# Freqy_Lights_1v1.net
KiCad netlist of a schematic drawn in EAGLE
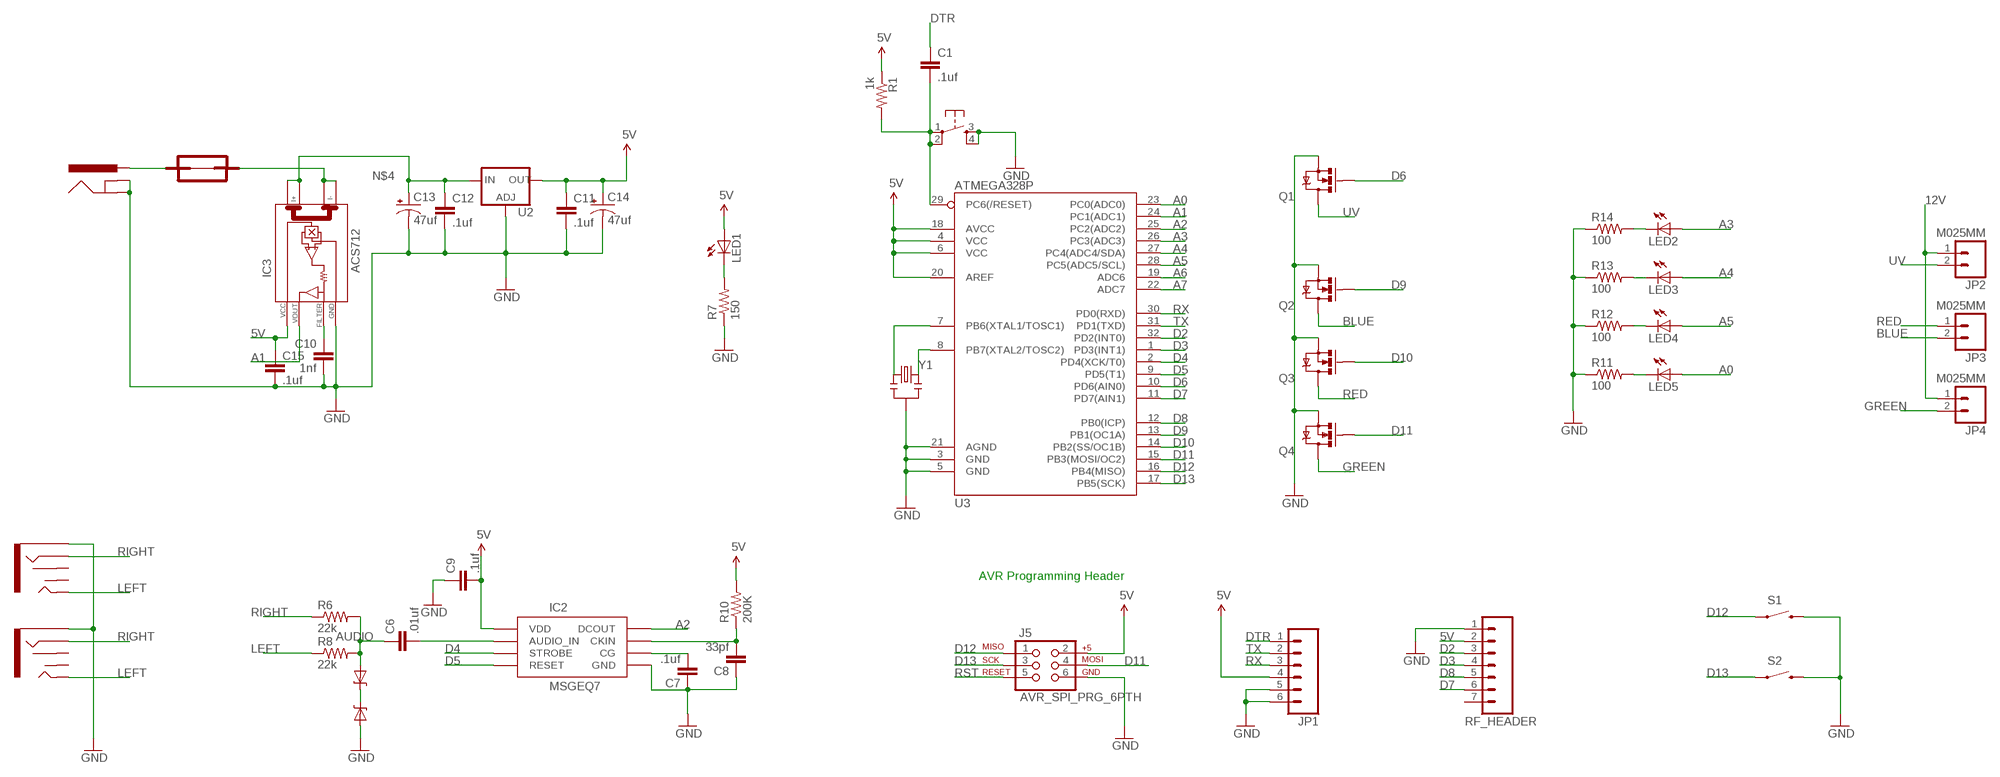
[diagram p0: schematic, sheet 1]

(export (version "E")
  (design (tool "Eeschema 10.0.6"))
  (components
    (comp (ref "AJ1")
      (value "SC1488-1-ND_SMD_AUDIO_3.5")
      (footprint "eagle-import:3.5MM_SMD_AUDIO_SC1488-1-ND")
      (libsource (lib "eagle-import") (part "SC1488-1-ND_SMD_AUDIO_3.5"))
    )
    (comp (ref "AJ2")
      (value "SC1488-1-ND_SMD_AUDIO_3.5")
      (footprint "eagle-import:3.5MM_SMD_AUDIO_SC1488-1-ND")
      (libsource (lib "eagle-import") (part "SC1488-1-ND_SMD_AUDIO_3.5"))
    )
    (comp (ref "BJ1")
      (value "CP-202BH-ND_POWERJACK")
      (footprint "eagle-import:POWER_JACK_CP-202BH-ND")
      (libsource (lib "eagle-import") (part "CP-202BH-ND_POWERJACK"))
    )
    (comp (ref "C1")
      (value ".1uf")
      (footprint "eagle-import:1206")
      (libsource (lib "eagle-import") (part "CAP1206"))
    )
    (comp (ref "C6")
      (value ".01uf")
      (footprint "eagle-import:1206")
      (libsource (lib "eagle-import") (part "CAP1206"))
    )
    (comp (ref "C7")
      (value ".1uf")
      (footprint "eagle-import:1206")
      (libsource (lib "eagle-import") (part "CAP1206"))
    )
    (comp (ref "C8")
      (value "33pf")
      (footprint "eagle-import:1206")
      (libsource (lib "eagle-import") (part "CAP1206"))
    )
    (comp (ref "C9")
      (value ".1uf")
      (footprint "eagle-import:1206")
      (libsource (lib "eagle-import") (part "CAP1206"))
    )
    (comp (ref "C10")
      (value "1nf")
      (footprint "eagle-import:1206")
      (libsource (lib "eagle-import") (part "CAP1206"))
    )
    (comp (ref "C11")
      (value ".1uf")
      (footprint "eagle-import:1206")
      (libsource (lib "eagle-import") (part "CAP1206"))
    )
    (comp (ref "C12")
      (value ".1uf")
      (footprint "eagle-import:1206")
      (libsource (lib "eagle-import") (part "CAP1206"))
    )
    (comp (ref "C13")
      (value "47uf")
      (footprint "eagle-import:SMD_47UF_CAP_493-2202-1-ND")
      (libsource (lib "eagle-import") (part "493-2202-1-ND_SMD_CAP"))
    )
    (comp (ref "C14")
      (value "47uf")
      (footprint "eagle-import:SMD_47UF_CAP_493-2202-1-ND")
      (libsource (lib "eagle-import") (part "493-2202-1-ND_SMD_CAP"))
    )
    (comp (ref "C15")
      (value ".1uf")
      (footprint "eagle-import:1206")
      (libsource (lib "eagle-import") (part "CAP1206"))
    )
    (comp (ref "F1")
      (value "SSQ12")
      (footprint "eagle-import:SSQ12")
      (libsource (lib "eagle-import") (part "SSQ12"))
    )
    (comp (ref "IC2")
      (value "MSGEQ7SOIC")
      (footprint "eagle-import:SOIC8")
      (libsource (lib "eagle-import") (part "MSGEQ7SOIC"))
    )
    (comp (ref "IC3")
      (value "ACS712")
      (footprint "eagle-import:SO08")
      (libsource (lib "eagle-import") (part "ACS712"))
    )
    (comp (ref "J5")
      (value "AVR_SPI_PRG_6PTH")
      (footprint "eagle-import:2X3")
      (libsource (lib "eagle-import") (part "AVR_SPI_PRG_6PTH"))
    )
    (comp (ref "JP1")
      (value "M06SIP")
      (footprint "eagle-import:1X06")
      (libsource (lib "eagle-import") (part "M06SIP"))
    )
    (comp (ref "JP2")
      (value "M025MM")
      (footprint "eagle-import:SCREWTERMINAL-5MM-2")
      (libsource (lib "eagle-import") (part "M025MM"))
    )
    (comp (ref "JP3")
      (value "M025MM")
      (footprint "eagle-import:SCREWTERMINAL-5MM-2")
      (libsource (lib "eagle-import") (part "M025MM"))
    )
    (comp (ref "JP4")
      (value "M025MM")
      (footprint "eagle-import:SCREWTERMINAL-5MM-2")
      (libsource (lib "eagle-import") (part "M025MM"))
    )
    (comp (ref "LED1")
      (value "LED1206")
      (footprint "eagle-import:LED-1206")
      (libsource (lib "eagle-import") (part "LED1206"))
    )
    (comp (ref "LED2")
      (value "LED1206")
      (footprint "eagle-import:LED-1206")
      (libsource (lib "eagle-import") (part "LED1206"))
    )
    (comp (ref "LED3")
      (value "LED1206")
      (footprint "eagle-import:LED-1206")
      (libsource (lib "eagle-import") (part "LED1206"))
    )
    (comp (ref "LED4")
      (value "LED1206")
      (footprint "eagle-import:LED-1206")
      (libsource (lib "eagle-import") (part "LED1206"))
    )
    (comp (ref "LED5")
      (value "LED1206")
      (footprint "eagle-import:LED-1206")
      (libsource (lib "eagle-import") (part "LED1206"))
    )
    (comp (ref "P1")
      (value "CKN9085CT-ND_SMT_PUSHBUTTON")
      (footprint "eagle-import:SMT_PUSHBUTTON_CKN9085CT-ND")
      (libsource (lib "eagle-import") (part "CKN9085CT-ND_SMT_PUSHBUTTON"))
    )
    (comp (ref "Q1")
      (value "MOSFET-NCHANNELBSS138")
      (footprint "eagle-import:SOT23")
      (libsource (lib "eagle-import") (part "MOSFET-NCHANNELBSS138"))
    )
    (comp (ref "Q2")
      (value "MOSFET-NCHANNELBSS138")
      (footprint "eagle-import:SOT23")
      (libsource (lib "eagle-import") (part "MOSFET-NCHANNELBSS138"))
    )
    (comp (ref "Q3")
      (value "MOSFET-NCHANNELBSS138")
      (footprint "eagle-import:SOT23")
      (libsource (lib "eagle-import") (part "MOSFET-NCHANNELBSS138"))
    )
    (comp (ref "Q4")
      (value "MOSFET-NCHANNELBSS138")
      (footprint "eagle-import:SOT23")
      (libsource (lib "eagle-import") (part "MOSFET-NCHANNELBSS138"))
    )
    (comp (ref "R1")
      (value "1k")
      (footprint "eagle-import:1206")
      (libsource (lib "eagle-import") (part "RESISTOR1206"))
    )
    (comp (ref "R6")
      (value "22k")
      (footprint "eagle-import:1206")
      (libsource (lib "eagle-import") (part "RESISTOR1206"))
    )
    (comp (ref "R7")
      (value "150")
      (footprint "eagle-import:1206")
      (libsource (lib "eagle-import") (part "RESISTOR1206"))
    )
    (comp (ref "R8")
      (value "22k")
      (footprint "eagle-import:1206")
      (libsource (lib "eagle-import") (part "RESISTOR1206"))
    )
    (comp (ref "R10")
      (value "200K")
      (footprint "eagle-import:1206")
      (libsource (lib "eagle-import") (part "RESISTOR1206"))
    )
    (comp (ref "R11")
      (value "100")
      (footprint "eagle-import:1206")
      (libsource (lib "eagle-import") (part "RESISTOR1206"))
    )
    (comp (ref "R12")
      (value "100")
      (footprint "eagle-import:1206")
      (libsource (lib "eagle-import") (part "RESISTOR1206"))
    )
    (comp (ref "R13")
      (value "100")
      (footprint "eagle-import:1206")
      (libsource (lib "eagle-import") (part "RESISTOR1206"))
    )
    (comp (ref "R14")
      (value "100")
      (footprint "eagle-import:1206")
      (libsource (lib "eagle-import") (part "RESISTOR1206"))
    )
    (comp (ref "RF_HEADER")
      (value "M07")
      (footprint "eagle-import:1X07")
      (libsource (lib "eagle-import") (part "M07"))
    )
    (comp (ref "S1")
      (value "SWITCH-MOMENTARY-2PTH")
      (footprint "eagle-import:TACTILE-PTH")
      (libsource (lib "eagle-import") (part "SWITCH-MOMENTARY-2PTH"))
    )
    (comp (ref "S2")
      (value "SWITCH-MOMENTARY-2PTH")
      (footprint "eagle-import:TACTILE-PTH")
      (libsource (lib "eagle-import") (part "SWITCH-MOMENTARY-2PTH"))
    )
    (comp (ref "U$10")
      (value "MM3Z3V3ST1GOSCT-ND_3V_DIODE")
      (footprint "eagle-import:3V_DIODE_MM3Z3V3ST1GOSCT-ND")
      (libsource (lib "eagle-import") (part "MM3Z3V3ST1GOSCT-ND_3V_DIODE"))
    )
    (comp (ref "U$11")
      (value "MM3Z3V3ST1GOSCT-ND_3V_DIODE")
      (footprint "eagle-import:3V_DIODE_MM3Z3V3ST1GOSCT-ND")
      (libsource (lib "eagle-import") (part "MM3Z3V3ST1GOSCT-ND_3V_DIODE"))
    )
    (comp (ref "U2")
      (value "V_REG_317SMD")
      (footprint "eagle-import:SOT223")
      (libsource (lib "eagle-import") (part "V_REG_317SMD"))
    )
    (comp (ref "U3")
      (value "ATMEGA328P")
      (footprint "eagle-import:TQFP32-08")
      (libsource (lib "eagle-import") (part "ATMEGA328_SMT"))
    )
    (comp (ref "Y1")
      (value "RESONATORPTH")
      (footprint "eagle-import:RESONATOR-PTH")
      (libsource (lib "eagle-import") (part "RESONATORPTH"))
    )
  )
  (nets
    (net (code "1") (name "/12V") (class "Default")
      (node (ref "C12") (pin "1") (pinfunction "1_1") (pintype "passive"))
      (node (ref "C13") (pin "P$2") (pinfunction "+_P$2") (pintype "passive"))
      (node (ref "IC3") (pin "1") (pinfunction "I+_0_1") (pintype "bidirectional"))
      (node (ref "IC3") (pin "2") (pinfunction "I+_1_2") (pintype "bidirectional"))
      (node (ref "JP2") (pin "1") (pinfunction "1_1") (pintype "passive"))
      (node (ref "JP4") (pin "1") (pinfunction "1_1") (pintype "passive"))
      (node (ref "U2") (pin "3") (pinfunction "IN_3") (pintype "input"))
    )
    (net (code "2") (name "/A0") (class "Default")
      (node (ref "LED5") (pin "A") (pinfunction "A_A") (pintype "passive"))
      (node (ref "U3") (pin "23") (pinfunction "PC0(ADC0)_23") (pintype "bidirectional"))
    )
    (net (code "3") (name "/A1") (class "Default")
      (node (ref "IC3") (pin "7") (pinfunction "VOUT_7") (pintype "output"))
      (node (ref "U3") (pin "24") (pinfunction "PC1(ADC1)_24") (pintype "bidirectional"))
    )
    (net (code "4") (name "/A2") (class "Default")
      (node (ref "IC2") (pin "3") (pinfunction "DCOUT_3") (pintype "bidirectional"))
      (node (ref "U3") (pin "25") (pinfunction "PC2(ADC2)_25") (pintype "bidirectional"))
    )
    (net (code "5") (name "/A3") (class "Default")
      (node (ref "LED2") (pin "A") (pinfunction "A_A") (pintype "passive"))
      (node (ref "U3") (pin "26") (pinfunction "PC3(ADC3)_26") (pintype "bidirectional"))
    )
    (net (code "6") (name "/A4") (class "Default")
      (node (ref "LED3") (pin "A") (pinfunction "A_A") (pintype "passive"))
      (node (ref "U3") (pin "27") (pinfunction "PC4(ADC4/SDA)_27") (pintype "bidirectional"))
    )
    (net (code "7") (name "/A5") (class "Default")
      (node (ref "LED4") (pin "A") (pinfunction "A_A") (pintype "passive"))
      (node (ref "U3") (pin "28") (pinfunction "PC5(ADC5/SCL)_28") (pintype "bidirectional"))
    )
    (net (code "8") (name "/A6") (class "Default")
      (node (ref "U3") (pin "19") (pinfunction "ADC6_19") (pintype "bidirectional"))
    )
    (net (code "9") (name "/A7") (class "Default")
      (node (ref "U3") (pin "22") (pinfunction "ADC7_22") (pintype "bidirectional"))
    )
    (net (code "10") (name "/AUDIO") (class "Default")
      (node (ref "C6") (pin "1") (pinfunction "1_1") (pintype "passive"))
      (node (ref "R6") (pin "2") (pinfunction "2_2") (pintype "passive"))
      (node (ref "R8") (pin "2") (pinfunction "2_2") (pintype "passive"))
      (node (ref "U$11") (pin "P$2") (pinfunction "A_P$2") (pintype "passive"))
    )
    (net (code "11") (name "/BLUE") (class "Default")
      (node (ref "JP3") (pin "2") (pinfunction "2_2") (pintype "passive"))
      (node (ref "Q2") (pin "3") (pinfunction "D_3") (pintype "passive"))
    )
    (net (code "12") (name "/D2") (class "Default")
      (node (ref "RF_HEADER") (pin "3") (pinfunction "3_3") (pintype "passive"))
      (node (ref "U3") (pin "32") (pinfunction "PD2(INT0)_32") (pintype "bidirectional"))
    )
    (net (code "13") (name "/D3") (class "Default")
      (node (ref "RF_HEADER") (pin "4") (pinfunction "4_4") (pintype "passive"))
      (node (ref "U3") (pin "1") (pinfunction "PD3(INT1)_1") (pintype "bidirectional"))
    )
    (net (code "14") (name "/D4") (class "Default")
      (node (ref "IC2") (pin "4") (pinfunction "STROBE_4") (pintype "input"))
      (node (ref "U3") (pin "2") (pinfunction "PD4(XCK/T0)_2") (pintype "bidirectional"))
    )
    (net (code "15") (name "/D5") (class "Default")
      (node (ref "IC2") (pin "7") (pinfunction "RESET_7") (pintype "input"))
      (node (ref "U3") (pin "9") (pinfunction "PD5(T1)_9") (pintype "bidirectional"))
    )
    (net (code "16") (name "/D6") (class "Default")
      (node (ref "Q1") (pin "1") (pinfunction "G_1") (pintype "passive"))
      (node (ref "U3") (pin "10") (pinfunction "PD6(AIN0)_10") (pintype "bidirectional"))
    )
    (net (code "17") (name "/D7") (class "Default")
      (node (ref "RF_HEADER") (pin "6") (pinfunction "6_6") (pintype "passive"))
      (node (ref "U3") (pin "11") (pinfunction "PD7(AIN1)_11") (pintype "bidirectional"))
    )
    (net (code "18") (name "/D8") (class "Default")
      (node (ref "RF_HEADER") (pin "5") (pinfunction "5_5") (pintype "passive"))
      (node (ref "U3") (pin "12") (pinfunction "PB0(ICP)_12") (pintype "bidirectional"))
    )
    (net (code "19") (name "/D9") (class "Default")
      (node (ref "Q2") (pin "1") (pinfunction "G_1") (pintype "passive"))
      (node (ref "U3") (pin "13") (pinfunction "PB1(OC1A)_13") (pintype "bidirectional"))
    )
    (net (code "20") (name "/D10") (class "Default")
      (node (ref "Q3") (pin "1") (pinfunction "G_1") (pintype "passive"))
      (node (ref "U3") (pin "14") (pinfunction "PB2(SS/OC1B)_14") (pintype "bidirectional"))
    )
    (net (code "21") (name "/D11") (class "Default")
      (node (ref "J5") (pin "4") (pinfunction "4_4") (pintype "passive"))
      (node (ref "Q4") (pin "1") (pinfunction "G_1") (pintype "passive"))
      (node (ref "U3") (pin "15") (pinfunction "PB3(MOSI/OC2)_15") (pintype "bidirectional"))
    )
    (net (code "22") (name "/D12") (class "Default")
      (node (ref "J5") (pin "1") (pinfunction "1_1") (pintype "passive"))
      (node (ref "S1") (pin "1") (pinfunction "1_1") (pintype "passive"))
      (node (ref "U3") (pin "16") (pinfunction "PB4(MISO)_16") (pintype "bidirectional"))
    )
    (net (code "23") (name "/D13") (class "Default")
      (node (ref "J5") (pin "3") (pinfunction "3_3") (pintype "passive"))
      (node (ref "S2") (pin "1") (pinfunction "1_1") (pintype "passive"))
      (node (ref "U3") (pin "17") (pinfunction "PB5(SCK)_17") (pintype "bidirectional"))
    )
    (net (code "24") (name "/DTR") (class "Default")
      (node (ref "C1") (pin "1") (pinfunction "1_1") (pintype "passive"))
      (node (ref "JP1") (pin "1") (pinfunction "1_1") (pintype "passive"))
    )
    (net (code "25") (name "/GREEN") (class "Default")
      (node (ref "JP4") (pin "2") (pinfunction "2_2") (pintype "passive"))
      (node (ref "Q4") (pin "3") (pinfunction "D_3") (pintype "passive"))
    )
    (net (code "26") (name "/LEFT") (class "Default")
      (node (ref "AJ1") (pin "TIP") (pinfunction "TIP_TIP") (pintype "bidirectional"))
      (node (ref "AJ2") (pin "TIP") (pinfunction "TIP_TIP") (pintype "bidirectional"))
      (node (ref "R8") (pin "1") (pinfunction "1_1") (pintype "passive"))
    )
    (net (code "27") (name "/N$4") (class "Default")
      (node (ref "F1") (pin "P$2") (pinfunction "P$2_P$2") (pintype "bidirectional"))
      (node (ref "IC3") (pin "3") (pinfunction "I-_0_3") (pintype "bidirectional"))
      (node (ref "IC3") (pin "4") (pinfunction "I-_1_4") (pintype "bidirectional"))
    )
    (net (code "28") (name "/RED") (class "Default")
      (node (ref "JP3") (pin "1") (pinfunction "1_1") (pintype "passive"))
      (node (ref "Q3") (pin "3") (pinfunction "D_3") (pintype "passive"))
    )
    (net (code "29") (name "/RIGHT") (class "Default")
      (node (ref "AJ1") (pin "SLEEVE") (pinfunction "SLEEVE_SLEEVE") (pintype "bidirectional"))
      (node (ref "AJ2") (pin "SLEEVE") (pinfunction "SLEEVE_SLEEVE") (pintype "bidirectional"))
      (node (ref "R6") (pin "1") (pinfunction "1_1") (pintype "passive"))
    )
    (net (code "30") (name "/RST") (class "Default")
      (node (ref "C1") (pin "2") (pinfunction "2_2") (pintype "passive"))
      (node (ref "J5") (pin "5") (pinfunction "5_5") (pintype "passive"))
      (node (ref "P1") (pin "1") (pinfunction "1_1") (pintype "passive"))
      (node (ref "P1") (pin "2") (pinfunction "2_2") (pintype "passive"))
      (node (ref "R1") (pin "2") (pinfunction "2_2") (pintype "passive"))
      (node (ref "U3") (pin "29") (pinfunction "PC6(/RESET)_29") (pintype "bidirectional"))
    )
    (net (code "31") (name "/RX") (class "Default")
      (node (ref "JP1") (pin "3") (pinfunction "3_3") (pintype "passive"))
      (node (ref "U3") (pin "30") (pinfunction "PD0(RXD)_30") (pintype "bidirectional"))
    )
    (net (code "32") (name "/TX") (class "Default")
      (node (ref "JP1") (pin "2") (pinfunction "2_2") (pintype "passive"))
      (node (ref "U3") (pin "31") (pinfunction "PD1(TXD)_31") (pintype "bidirectional"))
    )
    (net (code "33") (name "/UV") (class "Default")
      (node (ref "JP2") (pin "2") (pinfunction "2_2") (pintype "passive"))
      (node (ref "Q1") (pin "3") (pinfunction "D_3") (pintype "passive"))
    )
    (net (code "34") (name "5V") (class "Default")
      (node (ref "C11") (pin "1") (pinfunction "1_1") (pintype "passive"))
      (node (ref "C14") (pin "P$2") (pinfunction "+_P$2") (pintype "passive"))
      (node (ref "C15") (pin "1") (pinfunction "1_1") (pintype "passive"))
      (node (ref "C9") (pin "2") (pinfunction "2_2") (pintype "passive"))
      (node (ref "IC2") (pin "1") (pinfunction "VDD_1") (pintype "input"))
      (node (ref "IC3") (pin "8") (pinfunction "VCC_8") (pintype "power_in"))
      (node (ref "J5") (pin "2") (pinfunction "2_2") (pintype "passive"))
      (node (ref "JP1") (pin "4") (pinfunction "4_4") (pintype "passive"))
      (node (ref "LED1") (pin "A") (pinfunction "A_A") (pintype "passive"))
      (node (ref "R1") (pin "1") (pinfunction "1_1") (pintype "passive"))
      (node (ref "R10") (pin "2") (pinfunction "2_2") (pintype "passive"))
      (node (ref "RF_HEADER") (pin "2") (pinfunction "2_2") (pintype "passive"))
      (node (ref "U2") (pin "2") (pinfunction "OUT_2") (pintype "output"))
      (node (ref "U3") (pin "18") (pinfunction "AVCC_18") (pintype "bidirectional"))
      (node (ref "U3") (pin "20") (pinfunction "AREF_20") (pintype "bidirectional"))
      (node (ref "U3") (pin "4") (pinfunction "VCC_4") (pintype "bidirectional"))
      (node (ref "U3") (pin "6") (pinfunction "VCC_6") (pintype "bidirectional"))
    )
    (net (code "35") (name "GND") (class "Default")
      (node (ref "AJ1") (pin "RING") (pinfunction "RING_RING") (pintype "bidirectional"))
      (node (ref "AJ2") (pin "RING") (pinfunction "RING_RING") (pintype "bidirectional"))
      (node (ref "BJ1") (pin "GND") (pinfunction "GND_GND") (pintype "bidirectional"))
      (node (ref "BJ1") (pin "GNDBRK") (pinfunction "GNDBREAK_GNDBRK") (pintype "bidirectional"))
      (node (ref "C10") (pin "2") (pinfunction "2_2") (pintype "passive"))
      (node (ref "C11") (pin "2") (pinfunction "2_2") (pintype "passive"))
      (node (ref "C12") (pin "2") (pinfunction "2_2") (pintype "passive"))
      (node (ref "C13") (pin "P$1") (pinfunction "-_P$1") (pintype "passive"))
      (node (ref "C14") (pin "P$1") (pinfunction "-_P$1") (pintype "passive"))
      (node (ref "C15") (pin "2") (pinfunction "2_2") (pintype "passive"))
      (node (ref "C7") (pin "1") (pinfunction "1_1") (pintype "passive"))
      (node (ref "C8") (pin "1") (pinfunction "1_1") (pintype "passive"))
      (node (ref "C9") (pin "1") (pinfunction "1_1") (pintype "passive"))
      (node (ref "IC2") (pin "2") (pinfunction "GND_2") (pintype "bidirectional"))
      (node (ref "IC3") (pin "5") (pinfunction "GND_5") (pintype "power_in"))
      (node (ref "J5") (pin "6") (pinfunction "6_6") (pintype "passive"))
      (node (ref "JP1") (pin "5") (pinfunction "5_5") (pintype "passive"))
      (node (ref "JP1") (pin "6") (pinfunction "6_6") (pintype "passive"))
      (node (ref "P1") (pin "3") (pinfunction "3_3") (pintype "passive"))
      (node (ref "P1") (pin "4") (pinfunction "4_4") (pintype "passive"))
      (node (ref "Q1") (pin "2") (pinfunction "S_2") (pintype "passive"))
      (node (ref "Q2") (pin "2") (pinfunction "S_2") (pintype "passive"))
      (node (ref "Q3") (pin "2") (pinfunction "S_2") (pintype "passive"))
      (node (ref "Q4") (pin "2") (pinfunction "S_2") (pintype "passive"))
      (node (ref "R11") (pin "1") (pinfunction "1_1") (pintype "passive"))
      (node (ref "R12") (pin "1") (pinfunction "1_1") (pintype "passive"))
      (node (ref "R13") (pin "1") (pinfunction "1_1") (pintype "passive"))
      (node (ref "R14") (pin "1") (pinfunction "1_1") (pintype "passive"))
      (node (ref "R7") (pin "1") (pinfunction "1_1") (pintype "passive"))
      (node (ref "RF_HEADER") (pin "1") (pinfunction "1_1") (pintype "passive"))
      (node (ref "S1") (pin "3") (pinfunction "2_3") (pintype "passive"))
      (node (ref "S2") (pin "3") (pinfunction "2_3") (pintype "passive"))
      (node (ref "U$10") (pin "P$2") (pinfunction "A_P$2") (pintype "passive"))
      (node (ref "U2") (pin "1") (pinfunction "ADJ_1") (pintype "input"))
      (node (ref "U3") (pin "21") (pinfunction "AGND_21") (pintype "bidirectional"))
      (node (ref "U3") (pin "3") (pinfunction "GND_3") (pintype "bidirectional"))
      (node (ref "U3") (pin "5") (pinfunction "GND_5") (pintype "bidirectional"))
      (node (ref "Y1") (pin "2") (pinfunction "2_2") (pintype "passive"))
    )
    (net (code "36") (name "Net-(BJ1-PadPWR)") (class "Default")
      (node (ref "BJ1") (pin "PWR") (pinfunction "PWR_PWR") (pintype "bidirectional"))
      (node (ref "F1") (pin "P$1") (pinfunction "P$1_P$1") (pintype "bidirectional"))
    )
    (net (code "37") (name "Net-(IC2-AUDIO_IN)") (class "Default")
      (node (ref "C6") (pin "2") (pinfunction "2_2") (pintype "passive"))
      (node (ref "IC2") (pin "5") (pinfunction "AUDIO_IN_5") (pintype "input"))
    )
    (net (code "38") (name "Net-(IC2-CG)") (class "Default")
      (node (ref "C7") (pin "2") (pinfunction "2_2") (pintype "passive"))
      (node (ref "IC2") (pin "6") (pinfunction "CG_6") (pintype "bidirectional"))
    )
    (net (code "39") (name "Net-(IC2-CKIN)") (class "Default")
      (node (ref "C8") (pin "2") (pinfunction "2_2") (pintype "passive"))
      (node (ref "IC2") (pin "8") (pinfunction "CKIN_8") (pintype "bidirectional"))
      (node (ref "R10") (pin "1") (pinfunction "1_1") (pintype "passive"))
    )
    (net (code "40") (name "Net-(IC3-FILTER)") (class "Default")
      (node (ref "C10") (pin "1") (pinfunction "1_1") (pintype "passive"))
      (node (ref "IC3") (pin "6") (pinfunction "FILTER_6") (pintype "bidirectional"))
    )
    (net (code "41") (name "Net-(LED1-PadC)") (class "Default")
      (node (ref "LED1") (pin "C") (pinfunction "C_C") (pintype "passive"))
      (node (ref "R7") (pin "2") (pinfunction "2_2") (pintype "passive"))
    )
    (net (code "42") (name "Net-(LED2-PadC)") (class "Default")
      (node (ref "LED2") (pin "C") (pinfunction "C_C") (pintype "passive"))
      (node (ref "R14") (pin "2") (pinfunction "2_2") (pintype "passive"))
    )
    (net (code "43") (name "Net-(LED3-PadC)") (class "Default")
      (node (ref "LED3") (pin "C") (pinfunction "C_C") (pintype "passive"))
      (node (ref "R13") (pin "2") (pinfunction "2_2") (pintype "passive"))
    )
    (net (code "44") (name "Net-(LED4-PadC)") (class "Default")
      (node (ref "LED4") (pin "C") (pinfunction "C_C") (pintype "passive"))
      (node (ref "R12") (pin "2") (pinfunction "2_2") (pintype "passive"))
    )
    (net (code "45") (name "Net-(LED5-PadC)") (class "Default")
      (node (ref "LED5") (pin "C") (pinfunction "C_C") (pintype "passive"))
      (node (ref "R11") (pin "2") (pinfunction "2_2") (pintype "passive"))
    )
    (net (code "46") (name "Net-(U$10-C)") (class "Default")
      (node (ref "U$10") (pin "P$1") (pinfunction "C_P$1") (pintype "passive"))
      (node (ref "U$11") (pin "P$1") (pinfunction "C_P$1") (pintype "passive"))
    )
    (net (code "47") (name "Net-(U3-PB6(XTAL1{slash}TOSC1))") (class "Default")
      (node (ref "U3") (pin "7") (pinfunction "PB6(XTAL1/TOSC1)_7") (pintype "bidirectional"))
      (node (ref "Y1") (pin "1") (pinfunction "1_1") (pintype "passive"))
    )
    (net (code "48") (name "Net-(U3-PB7(XTAL2{slash}TOSC2))") (class "Default")
      (node (ref "U3") (pin "8") (pinfunction "PB7(XTAL2/TOSC2)_8") (pintype "bidirectional"))
      (node (ref "Y1") (pin "3") (pinfunction "3_3") (pintype "passive"))
    )
    (net (code "49") (name "unconnected-(AJ1-PadRSH)") (class "Default")
      (node (ref "AJ1") (pin "RSH") (pinfunction "RSH_RSH") (pintype "bidirectional"))
    )
    (net (code "50") (name "unconnected-(AJ1-PadTSH)") (class "Default")
      (node (ref "AJ1") (pin "TSH") (pinfunction "TSH_TSH") (pintype "bidirectional"))
    )
    (net (code "51") (name "unconnected-(AJ2-PadRSH)") (class "Default")
      (node (ref "AJ2") (pin "RSH") (pinfunction "RSH_RSH") (pintype "bidirectional"))
    )
    (net (code "52") (name "unconnected-(AJ2-PadTSH)") (class "Default")
      (node (ref "AJ2") (pin "TSH") (pinfunction "TSH_TSH") (pintype "bidirectional"))
    )
    (net (code "53") (name "unconnected-(RF_HEADER-Pad7)") (class "Default")
      (node (ref "RF_HEADER") (pin "7") (pinfunction "7_7") (pintype "passive"))
    )
  )
)
